# battery-source-resistance-outline.net
KiCad netlist of a schematic drawn in EAGLE
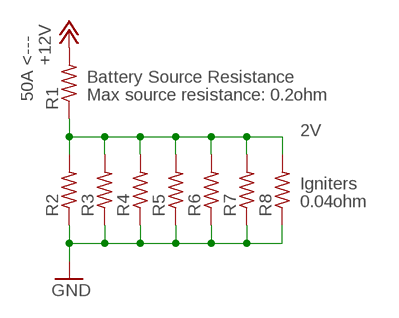
[diagram p0: schematic, sheet 1]

(export (version "E")
  (design (tool "Eeschema 10.0.6"))
  (components
    (comp (ref "R1")
      (value "R-US_0617/5V")
      (footprint "eagle-import:0617V")
      (libsource (lib "eagle-import") (part "R-US_0617/5V"))
    )
    (comp (ref "R2")
      (value "R-US_0617/5V")
      (footprint "eagle-import:0617V")
      (libsource (lib "eagle-import") (part "R-US_0617/5V"))
    )
    (comp (ref "R3")
      (value "R-US_0617/5V")
      (footprint "eagle-import:0617V")
      (libsource (lib "eagle-import") (part "R-US_0617/5V"))
    )
    (comp (ref "R4")
      (value "R-US_0617/5V")
      (footprint "eagle-import:0617V")
      (libsource (lib "eagle-import") (part "R-US_0617/5V"))
    )
    (comp (ref "R5")
      (value "R-US_0617/5V")
      (footprint "eagle-import:0617V")
      (libsource (lib "eagle-import") (part "R-US_0617/5V"))
    )
    (comp (ref "R6")
      (value "R-US_0617/5V")
      (footprint "eagle-import:0617V")
      (libsource (lib "eagle-import") (part "R-US_0617/5V"))
    )
    (comp (ref "R7")
      (value "R-US_0617/5V")
      (footprint "eagle-import:0617V")
      (libsource (lib "eagle-import") (part "R-US_0617/5V"))
    )
    (comp (ref "R8")
      (value "R-US_0617/5V")
      (footprint "eagle-import:0617V")
      (libsource (lib "eagle-import") (part "R-US_0617/5V"))
    )
  )
  (nets
    (net (code "1") (name "+12V") (class "Default")
      (node (ref "R1") (pin "2") (pinfunction "2_2") (pintype "passive"))
    )
    (net (code "2") (name "GND") (class "Default")
      (node (ref "R2") (pin "1") (pinfunction "1_1") (pintype "passive"))
      (node (ref "R3") (pin "1") (pinfunction "1_1") (pintype "passive"))
      (node (ref "R4") (pin "1") (pinfunction "1_1") (pintype "passive"))
      (node (ref "R5") (pin "1") (pinfunction "1_1") (pintype "passive"))
      (node (ref "R6") (pin "1") (pinfunction "1_1") (pintype "passive"))
      (node (ref "R7") (pin "1") (pinfunction "1_1") (pintype "passive"))
      (node (ref "R8") (pin "1") (pinfunction "1_1") (pintype "passive"))
    )
    (net (code "3") (name "Net-(R1-Pad1)") (class "Default")
      (node (ref "R1") (pin "1") (pinfunction "1_1") (pintype "passive"))
      (node (ref "R2") (pin "2") (pinfunction "2_2") (pintype "passive"))
      (node (ref "R3") (pin "2") (pinfunction "2_2") (pintype "passive"))
      (node (ref "R4") (pin "2") (pinfunction "2_2") (pintype "passive"))
      (node (ref "R5") (pin "2") (pinfunction "2_2") (pintype "passive"))
      (node (ref "R6") (pin "2") (pinfunction "2_2") (pintype "passive"))
      (node (ref "R7") (pin "2") (pinfunction "2_2") (pintype "passive"))
      (node (ref "R8") (pin "2") (pinfunction "2_2") (pintype "passive"))
    )
  )
)
